# Sheet1.net
KiCad netlist of a schematic drawn in Altium Designer
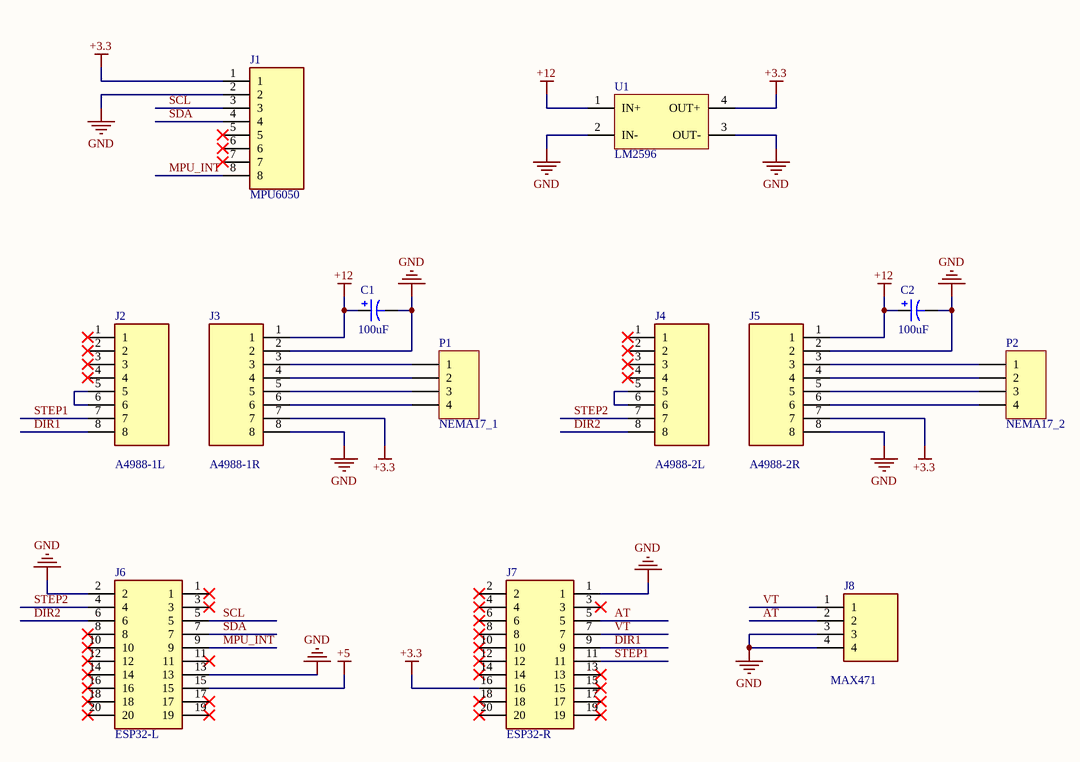
[diagram p0: Sheet1.SchDoc]

(export (version "E")
  (design (tool "Eeschema 10.0.6"))
  (components
    (comp (ref "C1")
      (value "100uF")
      (footprint "CAP AL TH D10 L2.5 H12.5 - duplicate")
      (description "Polarized Capacitor (Radial)")
      (fields (field (name "Comment") "Cap Pol1") (field (name "PUBLISHER") "Altium Limited"))
      (libsource (lib "Miscellaneous Devices") (part "Cap Pol1"))
    )
    (comp (ref "C2")
      (value "100uF")
      (footprint "CAP AL TH D10 L2.5 H12.5 - duplicate")
      (description "Polarized Capacitor (Radial)")
      (fields (field (name "Comment") "Cap Pol1") (field (name "PUBLISHER") "Altium Limited"))
      (libsource (lib "Miscellaneous Devices") (part "Cap Pol1"))
    )
    (comp (ref "J1")
      (value "MPU6050")
      (footprint "SamacSys:SSQ10803TSLL")
      (description "Connector")
      (fields
        (field (name "MANUFACTURER_PART_NUMBER") "SSQ-108-03-T-S-LL")
        (field (name "MOUSER PART NUMBER") "200-SSQ-108-03-TSLL")
      )
      (libsource (lib "*") (part "SSQ-108-03-T-S-LL"))
    )
    (comp (ref "J2")
      (value "A4988-1L")
      (footprint "SamacSys:SSQ10803TSLL")
      (description "Connector")
      (fields
        (field (name "MANUFACTURER_PART_NUMBER") "SSQ-108-03-T-S-LL")
        (field (name "MOUSER PART NUMBER") "200-SSQ-108-03-TSLL")
      )
      (libsource (lib "*") (part "SSQ-108-03-T-S-LL"))
    )
    (comp (ref "J3")
      (value "A4988-1R")
      (footprint "SamacSys:SSQ10803TSLL")
      (description "Connector")
      (fields
        (field (name "MANUFACTURER_PART_NUMBER") "SSQ-108-03-T-S-LL")
        (field (name "MOUSER PART NUMBER") "200-SSQ-108-03-TSLL")
      )
      (libsource (lib "") (part "SSQ-108-03-T-S-LL_1"))
    )
    (comp (ref "J4")
      (value "A4988-2L")
      (footprint "SamacSys:SSQ10803TSLL")
      (description "Connector")
      (fields
        (field (name "MANUFACTURER_PART_NUMBER") "SSQ-108-03-T-S-LL")
        (field (name "MOUSER PART NUMBER") "200-SSQ-108-03-TSLL")
      )
      (libsource (lib "*") (part "SSQ-108-03-T-S-LL"))
    )
    (comp (ref "J5")
      (value "A4988-2R")
      (footprint "SamacSys:SSQ10803TSLL")
      (description "Connector")
      (fields
        (field (name "MANUFACTURER_PART_NUMBER") "SSQ-108-03-T-S-LL")
        (field (name "MOUSER PART NUMBER") "200-SSQ-108-03-TSLL")
      )
      (libsource (lib "") (part "SSQ-108-03-T-S-LL_1"))
    )
    (comp (ref "J6")
      (value "ESP32-L")
      (footprint "SamacSys:RHDR20W64P254_2X10_2591X495X851P")
      (description "Connector")
      (fields
        (field (name "MANUFACTURER_PART_NUMBER") "SSQ-110-01-G-D-001")
        (field (name "MOUSER PART NUMBER") "200-SSQ11001GD001")
      )
      (libsource (lib "*") (part "SSQ-110-01-G-D-001"))
    )
    (comp (ref "J7")
      (value "ESP32-R")
      (footprint "SamacSys:RHDR20W64P254_2X10_2591X495X851P")
      (description "Connector")
      (fields
        (field (name "MANUFACTURER_PART_NUMBER") "SSQ-110-01-G-D-001")
        (field (name "MOUSER PART NUMBER") "200-SSQ11001GD001")
      )
      (libsource (lib "*") (part "SSQ-110-01-G-D-001"))
    )
    (comp (ref "J8")
      (value "MAX471")
      (footprint "SamacSys:RHDR4W64P0X254_1X4_1067X241X851P")
      (description "Connector")
      (fields (field (name "MANUFACTURER_PART_NUMBER") "SSQ-104-01-G-S-003"))
      (libsource (lib "*") (part "SSQ-104-01-G-S-003"))
    )
    (comp (ref "P1")
      (value "NEMA17_1")
      (footprint "JST XH B4B-XH-A")
      (description "Header, 4-Pin")
      (fields (field (name "PUBLISHER") "Altium Limited"))
      (libsource (lib "Miscellaneous Connectors") (part "Header 4"))
    )
    (comp (ref "P2")
      (value "NEMA17_2")
      (footprint "JST XH B4B-XH-A")
      (description "Header, 4-Pin")
      (fields (field (name "PUBLISHER") "Altium Limited"))
      (libsource (lib "Miscellaneous Connectors") (part "Header 4"))
    )
    (comp (ref "U1")
      (value "LM2596")
      (footprint "STEP_DOWN-LM2596")
      (libsource (lib "Kinetic_lib") (part "STEP_DOWN-LM2596"))
    )
  )
  (nets
    (net (code "1") (name "+3.3") (class "Default")
      (node (ref "J1") (pin "1") (pinfunction "1_1") (pintype "passive"))
      (node (ref "J3") (pin "7") (pinfunction "7_7") (pintype "passive"))
      (node (ref "J5") (pin "7") (pinfunction "7_7") (pintype "passive"))
      (node (ref "J7") (pin "16") (pinfunction "16_16") (pintype "passive"))
      (node (ref "U1") (pin "4") (pinfunction "OUT+_4") (pintype "passive"))
    )
    (net (code "2") (name "+5") (class "Default")
      (node (ref "J6") (pin "15") (pinfunction "15_15") (pintype "passive"))
    )
    (net (code "3") (name "+12") (class "Default")
      (node (ref "C1") (pin "1") (pinfunction "1_1") (pintype "passive"))
      (node (ref "C2") (pin "1") (pinfunction "1_1") (pintype "passive"))
      (node (ref "J3") (pin "1") (pinfunction "1_1") (pintype "passive"))
      (node (ref "J5") (pin "1") (pinfunction "1_1") (pintype "passive"))
      (node (ref "U1") (pin "1") (pinfunction "IN+_1") (pintype "passive"))
    )
    (net (code "4") (name "/AT") (class "Default")
      (node (ref "J7") (pin "5") (pinfunction "5_5") (pintype "passive"))
      (node (ref "J8") (pin "2") (pinfunction "2_2") (pintype "passive"))
    )
    (net (code "5") (name "/DIR1") (class "Default")
      (node (ref "J2") (pin "8") (pinfunction "8_8") (pintype "passive"))
      (node (ref "J7") (pin "9") (pinfunction "9_9") (pintype "passive"))
    )
    (net (code "6") (name "/DIR2") (class "Default")
      (node (ref "J4") (pin "8") (pinfunction "8_8") (pintype "passive"))
      (node (ref "J6") (pin "6") (pinfunction "6_6") (pintype "passive"))
    )
    (net (code "7") (name "/MPU_INT") (class "Default")
      (node (ref "J1") (pin "8") (pinfunction "8_8") (pintype "passive"))
      (node (ref "J6") (pin "9") (pinfunction "9_9") (pintype "passive"))
    )
    (net (code "8") (name "/SCL") (class "Default")
      (node (ref "J1") (pin "3") (pinfunction "3_3") (pintype "passive"))
      (node (ref "J6") (pin "5") (pinfunction "5_5") (pintype "passive"))
    )
    (net (code "9") (name "/SDA") (class "Default")
      (node (ref "J1") (pin "4") (pinfunction "4_4") (pintype "passive"))
      (node (ref "J6") (pin "7") (pinfunction "7_7") (pintype "passive"))
    )
    (net (code "10") (name "/STEP1") (class "Default")
      (node (ref "J2") (pin "7") (pinfunction "7_7") (pintype "passive"))
      (node (ref "J7") (pin "11") (pinfunction "11_11") (pintype "passive"))
    )
    (net (code "11") (name "/STEP2") (class "Default")
      (node (ref "J4") (pin "7") (pinfunction "7_7") (pintype "passive"))
      (node (ref "J6") (pin "4") (pinfunction "4_4") (pintype "passive"))
    )
    (net (code "12") (name "/VT") (class "Default")
      (node (ref "J7") (pin "7") (pinfunction "7_7") (pintype "passive"))
      (node (ref "J8") (pin "1") (pinfunction "1_1") (pintype "passive"))
    )
    (net (code "13") (name "GND") (class "Default")
      (node (ref "C1") (pin "2") (pinfunction "2_2") (pintype "passive"))
      (node (ref "C2") (pin "2") (pinfunction "2_2") (pintype "passive"))
      (node (ref "J1") (pin "2") (pinfunction "2_2") (pintype "passive"))
      (node (ref "J3") (pin "2") (pinfunction "2_2") (pintype "passive"))
      (node (ref "J3") (pin "8") (pinfunction "8_8") (pintype "passive"))
      (node (ref "J5") (pin "2") (pinfunction "2_2") (pintype "passive"))
      (node (ref "J5") (pin "8") (pinfunction "8_8") (pintype "passive"))
      (node (ref "J6") (pin "13") (pinfunction "13_13") (pintype "passive"))
      (node (ref "J6") (pin "2") (pinfunction "2_2") (pintype "passive"))
      (node (ref "J7") (pin "1") (pinfunction "1_1") (pintype "passive"))
      (node (ref "J8") (pin "3") (pinfunction "3_3") (pintype "passive"))
      (node (ref "J8") (pin "4") (pinfunction "4_4") (pintype "passive"))
      (node (ref "U1") (pin "2") (pinfunction "IN-_2") (pintype "passive"))
      (node (ref "U1") (pin "3") (pinfunction "OUT-_3") (pintype "passive"))
    )
    (net (code "14") (name "Net-(J2-Pad5)") (class "Default")
      (node (ref "J2") (pin "5") (pinfunction "5_5") (pintype "passive"))
      (node (ref "J2") (pin "6") (pinfunction "6_6") (pintype "passive"))
    )
    (net (code "15") (name "Net-(J3-Pad3)") (class "Default")
      (node (ref "J3") (pin "3") (pinfunction "3_3") (pintype "passive"))
      (node (ref "P1") (pin "1") (pinfunction "1_1") (pintype "passive"))
    )
    (net (code "16") (name "Net-(J3-Pad4)") (class "Default")
      (node (ref "J3") (pin "4") (pinfunction "4_4") (pintype "passive"))
      (node (ref "P1") (pin "2") (pinfunction "2_2") (pintype "passive"))
    )
    (net (code "17") (name "Net-(J3-Pad5)") (class "Default")
      (node (ref "J3") (pin "5") (pinfunction "5_5") (pintype "passive"))
      (node (ref "P1") (pin "3") (pinfunction "3_3") (pintype "passive"))
    )
    (net (code "18") (name "Net-(J3-Pad6)") (class "Default")
      (node (ref "J3") (pin "6") (pinfunction "6_6") (pintype "passive"))
      (node (ref "P1") (pin "4") (pinfunction "4_4") (pintype "passive"))
    )
    (net (code "19") (name "Net-(J4-Pad5)") (class "Default")
      (node (ref "J4") (pin "5") (pinfunction "5_5") (pintype "passive"))
      (node (ref "J4") (pin "6") (pinfunction "6_6") (pintype "passive"))
    )
    (net (code "20") (name "Net-(J5-Pad3)") (class "Default")
      (node (ref "J5") (pin "3") (pinfunction "3_3") (pintype "passive"))
      (node (ref "P2") (pin "1") (pinfunction "1_1") (pintype "passive"))
    )
    (net (code "21") (name "Net-(J5-Pad4)") (class "Default")
      (node (ref "J5") (pin "4") (pinfunction "4_4") (pintype "passive"))
      (node (ref "P2") (pin "2") (pinfunction "2_2") (pintype "passive"))
    )
    (net (code "22") (name "Net-(J5-Pad5)") (class "Default")
      (node (ref "J5") (pin "5") (pinfunction "5_5") (pintype "passive"))
      (node (ref "P2") (pin "3") (pinfunction "3_3") (pintype "passive"))
    )
    (net (code "23") (name "Net-(J5-Pad6)") (class "Default")
      (node (ref "J5") (pin "6") (pinfunction "6_6") (pintype "passive"))
      (node (ref "P2") (pin "4") (pinfunction "4_4") (pintype "passive"))
    )
    (net (code "24") (name "unconnected-(J1-Pad5)") (class "Default")
      (node (ref "J1") (pin "5") (pinfunction "5_5") (pintype "passive+no_connect"))
    )
    (net (code "25") (name "unconnected-(J1-Pad6)") (class "Default")
      (node (ref "J1") (pin "6") (pinfunction "6_6") (pintype "passive+no_connect"))
    )
    (net (code "26") (name "unconnected-(J1-Pad7)") (class "Default")
      (node (ref "J1") (pin "7") (pinfunction "7_7") (pintype "passive+no_connect"))
    )
    (net (code "27") (name "unconnected-(J2-Pad1)") (class "Default")
      (node (ref "J2") (pin "1") (pinfunction "1_1") (pintype "passive+no_connect"))
    )
    (net (code "28") (name "unconnected-(J2-Pad2)") (class "Default")
      (node (ref "J2") (pin "2") (pinfunction "2_2") (pintype "passive+no_connect"))
    )
    (net (code "29") (name "unconnected-(J2-Pad3)") (class "Default")
      (node (ref "J2") (pin "3") (pinfunction "3_3") (pintype "passive+no_connect"))
    )
    (net (code "30") (name "unconnected-(J2-Pad4)") (class "Default")
      (node (ref "J2") (pin "4") (pinfunction "4_4") (pintype "passive+no_connect"))
    )
    (net (code "31") (name "unconnected-(J4-Pad1)") (class "Default")
      (node (ref "J4") (pin "1") (pinfunction "1_1") (pintype "passive+no_connect"))
    )
    (net (code "32") (name "unconnected-(J4-Pad2)") (class "Default")
      (node (ref "J4") (pin "2") (pinfunction "2_2") (pintype "passive+no_connect"))
    )
    (net (code "33") (name "unconnected-(J4-Pad3)") (class "Default")
      (node (ref "J4") (pin "3") (pinfunction "3_3") (pintype "passive+no_connect"))
    )
    (net (code "34") (name "unconnected-(J4-Pad4)") (class "Default")
      (node (ref "J4") (pin "4") (pinfunction "4_4") (pintype "passive+no_connect"))
    )
    (net (code "35") (name "unconnected-(J6-Pad1)") (class "Default")
      (node (ref "J6") (pin "1") (pinfunction "1_1") (pintype "passive+no_connect"))
    )
    (net (code "36") (name "unconnected-(J6-Pad3)") (class "Default")
      (node (ref "J6") (pin "3") (pinfunction "3_3") (pintype "passive+no_connect"))
    )
    (net (code "37") (name "unconnected-(J6-Pad8)") (class "Default")
      (node (ref "J6") (pin "8") (pinfunction "8_8") (pintype "passive+no_connect"))
    )
    (net (code "38") (name "unconnected-(J6-Pad10)") (class "Default")
      (node (ref "J6") (pin "10") (pinfunction "10_10") (pintype "passive+no_connect"))
    )
    (net (code "39") (name "unconnected-(J6-Pad11)") (class "Default")
      (node (ref "J6") (pin "11") (pinfunction "11_11") (pintype "passive+no_connect"))
    )
    (net (code "40") (name "unconnected-(J6-Pad12)") (class "Default")
      (node (ref "J6") (pin "12") (pinfunction "12_12") (pintype "passive+no_connect"))
    )
    (net (code "41") (name "unconnected-(J6-Pad14)") (class "Default")
      (node (ref "J6") (pin "14") (pinfunction "14_14") (pintype "passive+no_connect"))
    )
    (net (code "42") (name "unconnected-(J6-Pad16)") (class "Default")
      (node (ref "J6") (pin "16") (pinfunction "16_16") (pintype "passive+no_connect"))
    )
    (net (code "43") (name "unconnected-(J6-Pad17)") (class "Default")
      (node (ref "J6") (pin "17") (pinfunction "17_17") (pintype "passive+no_connect"))
    )
    (net (code "44") (name "unconnected-(J6-Pad18)") (class "Default")
      (node (ref "J6") (pin "18") (pinfunction "18_18") (pintype "passive+no_connect"))
    )
    (net (code "45") (name "unconnected-(J6-Pad19)") (class "Default")
      (node (ref "J6") (pin "19") (pinfunction "19_19") (pintype "passive+no_connect"))
    )
    (net (code "46") (name "unconnected-(J6-Pad20)") (class "Default")
      (node (ref "J6") (pin "20") (pinfunction "20_20") (pintype "passive+no_connect"))
    )
    (net (code "47") (name "unconnected-(J7-Pad2)") (class "Default")
      (node (ref "J7") (pin "2") (pinfunction "2_2") (pintype "passive+no_connect"))
    )
    (net (code "48") (name "unconnected-(J7-Pad3)") (class "Default")
      (node (ref "J7") (pin "3") (pinfunction "3_3") (pintype "passive+no_connect"))
    )
    (net (code "49") (name "unconnected-(J7-Pad4)") (class "Default")
      (node (ref "J7") (pin "4") (pinfunction "4_4") (pintype "passive+no_connect"))
    )
    (net (code "50") (name "unconnected-(J7-Pad6)") (class "Default")
      (node (ref "J7") (pin "6") (pinfunction "6_6") (pintype "passive+no_connect"))
    )
    (net (code "51") (name "unconnected-(J7-Pad8)") (class "Default")
      (node (ref "J7") (pin "8") (pinfunction "8_8") (pintype "passive+no_connect"))
    )
    (net (code "52") (name "unconnected-(J7-Pad10)") (class "Default")
      (node (ref "J7") (pin "10") (pinfunction "10_10") (pintype "passive+no_connect"))
    )
    (net (code "53") (name "unconnected-(J7-Pad12)") (class "Default")
      (node (ref "J7") (pin "12") (pinfunction "12_12") (pintype "passive+no_connect"))
    )
    (net (code "54") (name "unconnected-(J7-Pad13)") (class "Default")
      (node (ref "J7") (pin "13") (pinfunction "13_13") (pintype "passive+no_connect"))
    )
    (net (code "55") (name "unconnected-(J7-Pad14)") (class "Default")
      (node (ref "J7") (pin "14") (pinfunction "14_14") (pintype "passive+no_connect"))
    )
    (net (code "56") (name "unconnected-(J7-Pad15)") (class "Default")
      (node (ref "J7") (pin "15") (pinfunction "15_15") (pintype "passive+no_connect"))
    )
    (net (code "57") (name "unconnected-(J7-Pad17)") (class "Default")
      (node (ref "J7") (pin "17") (pinfunction "17_17") (pintype "passive+no_connect"))
    )
    (net (code "58") (name "unconnected-(J7-Pad18)") (class "Default")
      (node (ref "J7") (pin "18") (pinfunction "18_18") (pintype "passive+no_connect"))
    )
    (net (code "59") (name "unconnected-(J7-Pad19)") (class "Default")
      (node (ref "J7") (pin "19") (pinfunction "19_19") (pintype "passive+no_connect"))
    )
    (net (code "60") (name "unconnected-(J7-Pad20)") (class "Default")
      (node (ref "J7") (pin "20") (pinfunction "20_20") (pintype "passive+no_connect"))
    )
  )
)
